# sensor.net
KiCad netlist of a schematic drawn in Altium Designer
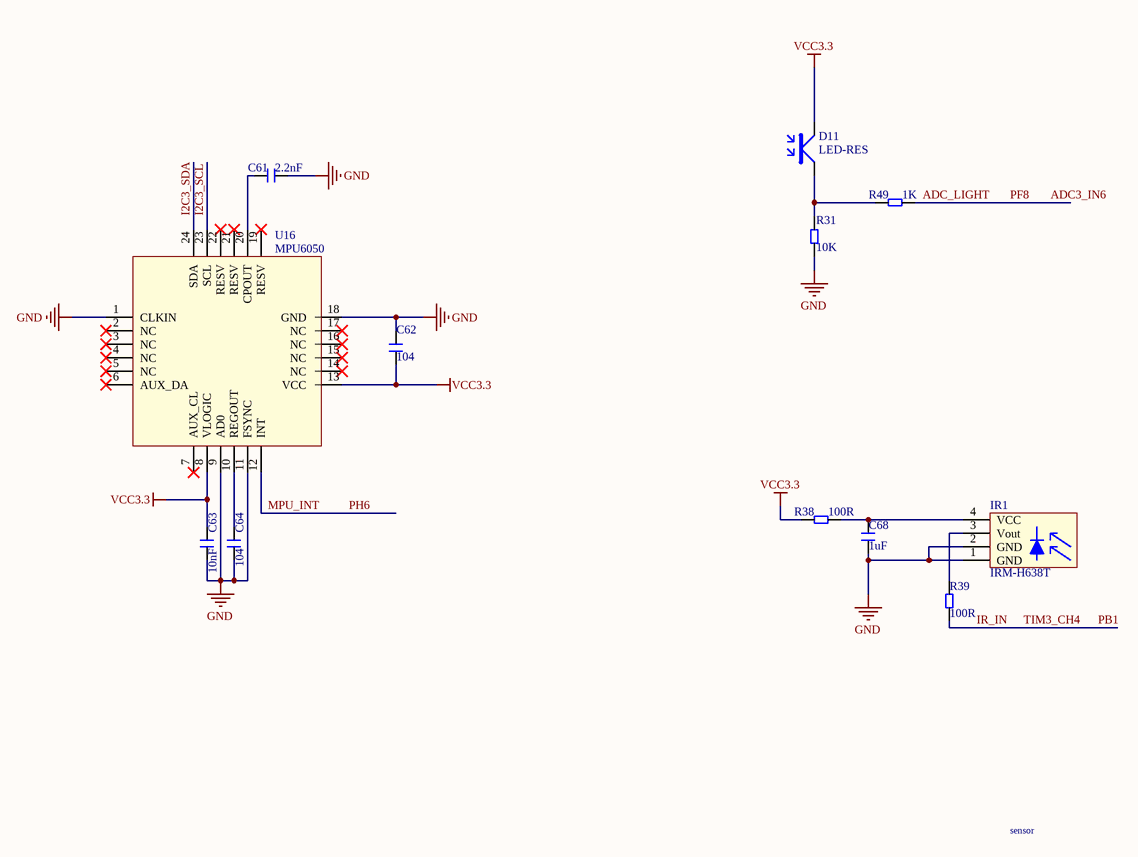
[diagram p0: sensor.SchDoc]

(export (version "E")
  (design (tool "Eeschema 10.0.6"))
  (components
    (comp (ref "C61") (value "2.2nF") (footprint "C 0603") (libsource (lib "Bison-Board") (part "CAP")))
    (comp (ref "C62") (value "104") (footprint "C 0603") (libsource (lib "Bison-Board") (part "CAP")))
    (comp (ref "C63") (value "10nF") (footprint "C 0603") (libsource (lib "Bison-Board") (part "CAP")))
    (comp (ref "C64") (value "104") (footprint "C 0603") (libsource (lib "Bison-Board") (part "CAP")))
    (comp (ref "C68") (value "1uF") (footprint "C 0603") (libsource (lib "squ-guiboard") (part "CAP")))
    (comp (ref "D11")
      (value "LED-RES")
      (footprint "LED 0805")
      (description "光敏传感器")
      (libsource (lib "squ-guiboard") (part "LRES"))
    )
    (comp (ref "IR1")
      (value "IRM-H638T")
      (footprint "IRM-H638T")
      (libsource (lib "squ-guiboard") (part "IRM-H638T"))
    )
    (comp (ref "R31") (value "10K") (footprint "R 0603") (libsource (lib "squ-guiboard") (part "RES")))
    (comp (ref "R38") (value "100R") (footprint "R 0603") (libsource (lib "squ-guiboard") (part "RES")))
    (comp (ref "R39") (value "100R") (footprint "R 0603") (libsource (lib "squ-guiboard") (part "RES")))
    (comp (ref "R49") (value "1K") (footprint "R 0603") (libsource (lib "squ-guiboard") (part "RES")))
    (comp (ref "U16")
      (value "MPU6050")
      (footprint "QFN24")
      (description "六轴姿态传感器")
      (libsource (lib "Bison-Board") (part "MPU6050"))
    )
  )
  (nets
    (net (code "1") (name "/ADC3_IN6") (class "Default") (node (ref "R49") (pin "1") (pintype "passive")))
    (net (code "2") (name "/I2C3_SCL") (class "Default")
      (node (ref "U16") (pin "23") (pinfunction "SCL_23") (pintype "passive"))
    )
    (net (code "3") (name "/I2C3_SDA") (class "Default")
      (node (ref "U16") (pin "24") (pinfunction "SDA_24") (pintype "passive"))
    )
    (net (code "4") (name "/IR_IN") (class "Default") (node (ref "R39") (pin "2") (pintype "passive")))
    (net (code "5") (name "/MPU_INT") (class "Default")
      (node (ref "U16") (pin "12") (pinfunction "INT_12") (pintype "passive"))
    )
    (net (code "6") (name "GND") (class "Default")
      (node (ref "C61") (pin "2") (pinfunction "2_2") (pintype "passive"))
      (node (ref "C62") (pin "2") (pinfunction "2_2") (pintype "passive"))
      (node (ref "C63") (pin "1") (pinfunction "1_1") (pintype "passive"))
      (node (ref "C64") (pin "1") (pinfunction "1_1") (pintype "passive"))
      (node (ref "C68") (pin "1") (pinfunction "1_1") (pintype "passive"))
      (node (ref "IR1") (pin "1") (pinfunction "GND_1") (pintype "passive"))
      (node (ref "IR1") (pin "2") (pinfunction "GND_2") (pintype "passive"))
      (node (ref "R31") (pin "1") (pintype "passive"))
      (node (ref "U16") (pin "1") (pinfunction "CLKIN_1") (pintype "passive"))
      (node (ref "U16") (pin "11") (pinfunction "FSYNC_11") (pintype "passive"))
      (node (ref "U16") (pin "18") (pinfunction "GND_18") (pintype "passive"))
      (node (ref "U16") (pin "9") (pinfunction "AD0_9") (pintype "passive"))
    )
    (net (code "7") (name "Net-(D11-Pad1)") (class "Default")
      (node (ref "D11") (pin "1") (pinfunction "1_1") (pintype "passive"))
      (node (ref "R31") (pin "2") (pintype "passive"))
      (node (ref "R49") (pin "2") (pintype "passive"))
    )
    (net (code "8") (name "Net-(IR1-VCC)") (class "Default")
      (node (ref "C68") (pin "2") (pinfunction "2_2") (pintype "passive"))
      (node (ref "IR1") (pin "4") (pinfunction "VCC_4") (pintype "passive"))
      (node (ref "R38") (pin "2") (pintype "passive"))
    )
    (net (code "9") (name "Net-(IR1-Vout)") (class "Default")
      (node (ref "IR1") (pin "3") (pinfunction "Vout_3") (pintype "passive"))
      (node (ref "R39") (pin "1") (pintype "passive"))
    )
    (net (code "10") (name "Net-(U16-CPOUT)") (class "Default")
      (node (ref "C61") (pin "1") (pinfunction "1_1") (pintype "passive"))
      (node (ref "U16") (pin "20") (pinfunction "CPOUT_20") (pintype "passive"))
    )
    (net (code "11") (name "Net-(U16-REGOUT)") (class "Default")
      (node (ref "C64") (pin "2") (pinfunction "2_2") (pintype "passive"))
      (node (ref "U16") (pin "10") (pinfunction "REGOUT_10") (pintype "passive"))
    )
    (net (code "12") (name "VCC3.3") (class "Default")
      (node (ref "C62") (pin "1") (pinfunction "1_1") (pintype "passive"))
      (node (ref "C63") (pin "2") (pinfunction "2_2") (pintype "passive"))
      (node (ref "D11") (pin "2") (pinfunction "2_2") (pintype "passive"))
      (node (ref "R38") (pin "1") (pintype "passive"))
      (node (ref "U16") (pin "13") (pinfunction "VCC_13") (pintype "passive"))
      (node (ref "U16") (pin "8") (pinfunction "VLOGIC_8") (pintype "passive"))
    )
    (net (code "13") (name "unconnected-(U16-AUX_CL-Pad7)") (class "Default")
      (node (ref "U16") (pin "7") (pinfunction "AUX_CL_7") (pintype "passive+no_connect"))
    )
    (net (code "14") (name "unconnected-(U16-AUX_DA-Pad6)") (class "Default")
      (node (ref "U16") (pin "6") (pinfunction "AUX_DA_6") (pintype "passive+no_connect"))
    )
    (net (code "15") (name "unconnected-(U16-NC-Pad2)") (class "Default")
      (node (ref "U16") (pin "2") (pinfunction "NC_2") (pintype "passive+no_connect"))
    )
    (net (code "16") (name "unconnected-(U16-NC-Pad3)") (class "Default")
      (node (ref "U16") (pin "3") (pinfunction "NC_3") (pintype "passive+no_connect"))
    )
    (net (code "17") (name "unconnected-(U16-NC-Pad4)") (class "Default")
      (node (ref "U16") (pin "4") (pinfunction "NC_4") (pintype "passive+no_connect"))
    )
    (net (code "18") (name "unconnected-(U16-NC-Pad5)") (class "Default")
      (node (ref "U16") (pin "5") (pinfunction "NC_5") (pintype "passive+no_connect"))
    )
    (net (code "19") (name "unconnected-(U16-NC-Pad14)") (class "Default")
      (node (ref "U16") (pin "14") (pinfunction "NC_14") (pintype "passive+no_connect"))
    )
    (net (code "20") (name "unconnected-(U16-NC-Pad15)") (class "Default")
      (node (ref "U16") (pin "15") (pinfunction "NC_15") (pintype "passive+no_connect"))
    )
    (net (code "21") (name "unconnected-(U16-NC-Pad16)") (class "Default")
      (node (ref "U16") (pin "16") (pinfunction "NC_16") (pintype "passive+no_connect"))
    )
    (net (code "22") (name "unconnected-(U16-NC-Pad17)") (class "Default")
      (node (ref "U16") (pin "17") (pinfunction "NC_17") (pintype "passive+no_connect"))
    )
    (net (code "23") (name "unconnected-(U16-RESV-Pad19)") (class "Default")
      (node (ref "U16") (pin "19") (pinfunction "RESV_19") (pintype "passive+no_connect"))
    )
    (net (code "24") (name "unconnected-(U16-RESV-Pad21)") (class "Default")
      (node (ref "U16") (pin "21") (pinfunction "RESV_21") (pintype "passive+no_connect"))
    )
    (net (code "25") (name "unconnected-(U16-RESV-Pad22)") (class "Default")
      (node (ref "U16") (pin "22") (pinfunction "RESV_22") (pintype "passive+no_connect"))
    )
  )
)
